# Mini_Voltmeter.net
KiCad netlist of a schematic drawn in Altium Designer
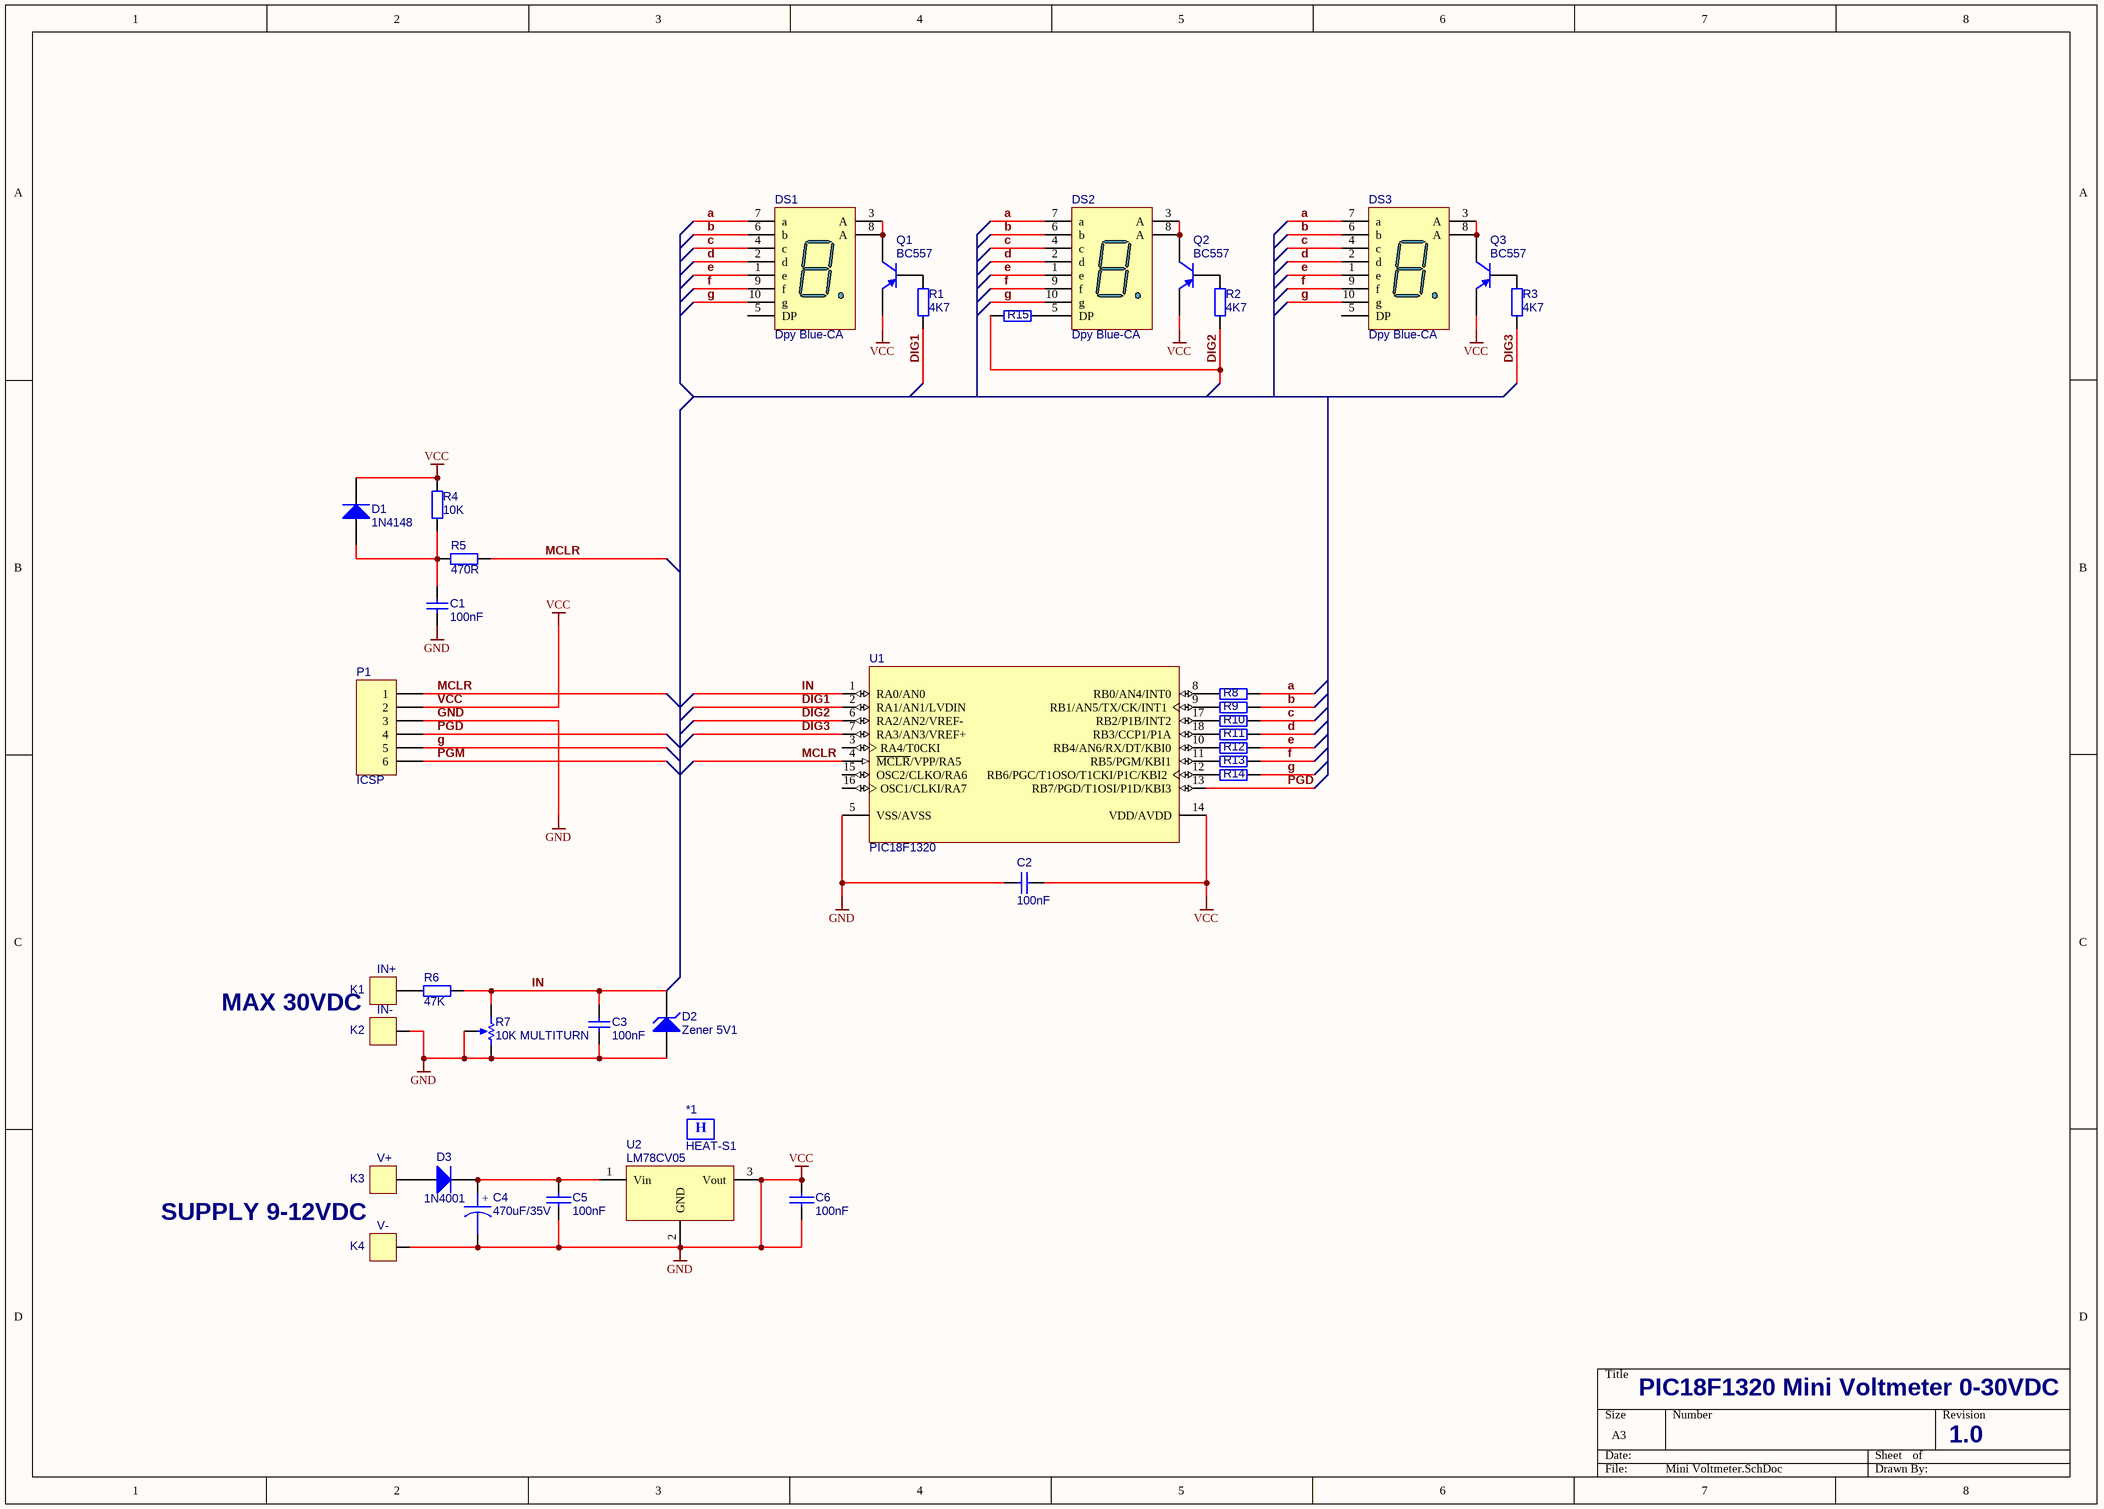
[diagram p0: Mini Voltmeter.SchDoc]

(export (version "E")
  (design (tool "Eeschema 10.0.6"))
  (components
    (comp (ref "*1")
      (value "HEAT-S1")
      (footprint "Heat_Sink1")
      (libsource (lib "SG_INTLIB") (part "HEAT-S1"))
    )
    (comp (ref "C1")
      (value "100nF")
      (footprint "RAD-0.3")
      (description "Capacitor")
      (fields (field (name "PUBLISHER") "Altium Limited"))
      (libsource (lib "Miscellaneous Devices") (part "Cap"))
    )
    (comp (ref "C2")
      (value "100nF")
      (footprint "RAD-0.3")
      (description "Capacitor")
      (fields (field (name "PUBLISHER") "Altium Limited"))
      (libsource (lib "Miscellaneous Devices") (part "Cap"))
    )
    (comp (ref "C3")
      (value "100nF")
      (footprint "RAD-0.3")
      (description "Capacitor")
      (fields (field (name "PUBLISHER") "Altium Limited"))
      (libsource (lib "Miscellaneous Devices") (part "Cap"))
    )
    (comp (ref "C4")
      (value "470uF/35V")
      (footprint "RB-10")
      (description "Capacitor")
      (libsource (lib "*") (part "CAPACITOR POL"))
    )
    (comp (ref "C5")
      (value "100nF")
      (footprint "RAD-0.1")
      (description "Capacitor")
      (libsource (lib "*") (part "CAP"))
    )
    (comp (ref "C6")
      (value "100nF")
      (footprint "RAD-0.1")
      (description "Capacitor")
      (libsource (lib "*") (part "CAP"))
    )
    (comp (ref "D1")
      (value "1N4148")
      (footprint "DO-35")
      (description "High Conductance Fast Diode")
      (fields (field (name "PUBLISHER") "Altium Limited"))
      (libsource (lib "Miscellaneous Devices") (part "Diode 1N914"))
    )
    (comp (ref "D2")
      (value "Zener 5V1")
      (description "Zener Diode")
      (fields (field (name "PUBLISHER") "Altium Limited"))
      (libsource (lib "Miscellaneous Devices") (part "D Zener"))
    )
    (comp (ref "D3")
      (value "1N4001")
      (footprint "DO-35")
      (description "High Conductance Fast Diode")
      (fields (field (name "PUBLISHER") "Altium Limited"))
      (libsource (lib "Miscellaneous Devices") (part "Diode 1N914"))
    )
    (comp (ref "DS1")
      (value "Dpy Blue-CA")
      (footprint "H")
      (description "14.2 mm General Purpose Blue 7-Segment Display: CA, RH DP, Gray Surface")
      (fields (field (name "PUBLISHER") "Altium Limited"))
      (libsource (lib "Miscellaneous Devices") (part "Dpy Blue-CA"))
    )
    (comp (ref "DS2")
      (value "Dpy Blue-CA")
      (footprint "H")
      (description "14.2 mm General Purpose Blue 7-Segment Display: CA, RH DP, Gray Surface")
      (fields (field (name "PUBLISHER") "Altium Limited"))
      (libsource (lib "Miscellaneous Devices") (part "Dpy Blue-CA"))
    )
    (comp (ref "DS3")
      (value "Dpy Blue-CA")
      (footprint "H")
      (description "14.2 mm General Purpose Blue 7-Segment Display: CA, RH DP, Gray Surface")
      (fields (field (name "PUBLISHER") "Altium Limited"))
      (libsource (lib "Miscellaneous Devices") (part "Dpy Blue-CA"))
    )
    (comp (ref "K1")
      (value "IN+")
      (footprint "CON2")
      (description "Connector")
      (libsource (lib "*") (part "CON1"))
    )
    (comp (ref "K2")
      (value "IN-")
      (footprint "CON2")
      (description "Connector")
      (libsource (lib "*") (part "CON1"))
    )
    (comp (ref "K3")
      (value "V+")
      (footprint "CON2")
      (description "Connector")
      (libsource (lib "*") (part "CON1"))
    )
    (comp (ref "K4")
      (value "V-")
      (footprint "CON2")
      (description "Connector")
      (libsource (lib "*") (part "CON1"))
    )
    (comp (ref "P1")
      (value "ICSP")
      (footprint "HDR1X6")
      (description "Header, 6-Pin")
      (fields (field (name "PUBLISHER") "Altium Limited"))
      (libsource (lib "Miscellaneous Connectors") (part "Header 6"))
    )
    (comp (ref "Q1")
      (value "BC557")
      (footprint "SOT54")
      (description "PNP General-purpose Transistor")
      (fields (field (name "PUBLISHER") "Altium Limited"))
      (libsource (lib "Philips Discrete BJT - Low Power") (part "BC557"))
    )
    (comp (ref "Q2")
      (value "BC557")
      (footprint "SOT54")
      (description "PNP General-purpose Transistor")
      (fields (field (name "PUBLISHER") "Altium Limited"))
      (libsource (lib "Philips Discrete BJT - Low Power") (part "BC557"))
    )
    (comp (ref "Q3")
      (value "BC557")
      (footprint "SOT54")
      (description "PNP General-purpose Transistor")
      (fields (field (name "PUBLISHER") "Altium Limited"))
      (libsource (lib "Philips Discrete BJT - Low Power") (part "BC557"))
    )
    (comp (ref "R1")
      (value "4K7")
      (footprint "AXIAL-0.4")
      (description "Resistor")
      (fields (field (name "PUBLISHER") "Altium Limited"))
      (libsource (lib "Miscellaneous Devices") (part "Res2"))
    )
    (comp (ref "R2")
      (value "4K7")
      (footprint "AXIAL-0.4")
      (description "Resistor")
      (fields (field (name "PUBLISHER") "Altium Limited"))
      (libsource (lib "Miscellaneous Devices") (part "Res2"))
    )
    (comp (ref "R3")
      (value "4K7")
      (footprint "AXIAL-0.4")
      (description "Resistor")
      (fields (field (name "PUBLISHER") "Altium Limited"))
      (libsource (lib "Miscellaneous Devices") (part "Res2"))
    )
    (comp (ref "R4")
      (value "10K")
      (footprint "AXIAL-0.4")
      (description "Resistor")
      (fields (field (name "PUBLISHER") "Altium Limited"))
      (libsource (lib "Miscellaneous Devices") (part "Res2"))
    )
    (comp (ref "R5")
      (value "470R")
      (footprint "AXIAL-0.4")
      (description "Resistor")
      (fields (field (name "PUBLISHER") "Altium Limited"))
      (libsource (lib "") (part "Res2_1"))
    )
    (comp (ref "R6")
      (value "47K")
      (footprint "AXIAL-0.4")
      (description "Resistor")
      (fields (field (name "PUBLISHER") "Altium Limited"))
      (libsource (lib "") (part "Res2_1"))
    )
    (comp (ref "R7")
      (value "10K MULTITURN")
      (footprint "VR5")
      (description "Potentiometer")
      (fields (field (name "PUBLISHER") "Altium Limited"))
      (libsource (lib "Miscellaneous Devices") (part "RPot"))
    )
    (comp (ref "R8")
      (value "220R")
      (footprint "AXIAL-0.4")
      (description "Resistor")
      (fields (field (name "PUBLISHER") "Altium Limited"))
      (libsource (lib "") (part "Res2_1"))
    )
    (comp (ref "R9")
      (value "220R")
      (footprint "AXIAL-0.4")
      (description "Resistor")
      (fields (field (name "PUBLISHER") "Altium Limited"))
      (libsource (lib "") (part "Res2_1"))
    )
    (comp (ref "R10")
      (value "220R")
      (footprint "AXIAL-0.4")
      (description "Resistor")
      (fields (field (name "PUBLISHER") "Altium Limited"))
      (libsource (lib "") (part "Res2_1"))
    )
    (comp (ref "R11")
      (value "220R")
      (footprint "AXIAL-0.4")
      (description "Resistor")
      (fields (field (name "PUBLISHER") "Altium Limited"))
      (libsource (lib "") (part "Res2_1"))
    )
    (comp (ref "R12")
      (value "220R")
      (footprint "AXIAL-0.4")
      (description "Resistor")
      (fields (field (name "PUBLISHER") "Altium Limited"))
      (libsource (lib "") (part "Res2_1"))
    )
    (comp (ref "R13")
      (value "220R")
      (footprint "AXIAL-0.4")
      (description "Resistor")
      (fields (field (name "PUBLISHER") "Altium Limited"))
      (libsource (lib "") (part "Res2_1"))
    )
    (comp (ref "R14")
      (value "220R")
      (footprint "AXIAL-0.4")
      (description "Resistor")
      (fields (field (name "PUBLISHER") "Altium Limited"))
      (libsource (lib "") (part "Res2_1"))
    )
    (comp (ref "R15")
      (value "220R")
      (footprint "AXIAL-0.4")
      (description "Resistor")
      (fields (field (name "PUBLISHER") "Altium Limited"))
      (libsource (lib "") (part "Res2_1"))
    )
    (comp (ref "U1")
      (value "PIC18F1320")
      (footprint "PDIP300-18")
      (fields (field (name "PUBLISHER") "Altium Limited"))
      (libsource (lib "Microchip Microcontroller 8-Bit PIC18") (part "PIC18F1320-E/P"))
    )
    (comp (ref "U2") (value "LM78CV05") (footprint "to-220") (libsource (lib "*") (part "VOLTREG")))
  )
  (nets
    (net (code "1") (name "/DIG1") (class "Default")
      (node (ref "R1") (pin "1") (pinfunction "1_1") (pintype "passive"))
      (node (ref "U1") (pin "2") (pinfunction "RA1/AN1/LVDIN_2") (pintype "bidirectional"))
    )
    (net (code "2") (name "/DIG2") (class "Default")
      (node (ref "R15") (pin "2") (pinfunction "2_2") (pintype "passive"))
      (node (ref "R2") (pin "1") (pinfunction "1_1") (pintype "passive"))
      (node (ref "U1") (pin "6") (pinfunction "RA2/AN2/VREF-_6") (pintype "bidirectional"))
    )
    (net (code "3") (name "/DIG3") (class "Default")
      (node (ref "R3") (pin "1") (pinfunction "1_1") (pintype "passive"))
      (node (ref "U1") (pin "7") (pinfunction "RA3/AN3/VREF+_7") (pintype "bidirectional"))
    )
    (net (code "4") (name "/IN") (class "Default")
      (node (ref "C3") (pin "2") (pinfunction "2_2") (pintype "passive"))
      (node (ref "D2") (pin "2") (pinfunction "K_2") (pintype "passive"))
      (node (ref "R6") (pin "1") (pinfunction "1_1") (pintype "passive"))
      (node (ref "R7") (pin "1") (pinfunction "TOP_1") (pintype "passive"))
      (node (ref "U1") (pin "1") (pinfunction "RA0/AN0_1") (pintype "bidirectional"))
    )
    (net (code "5") (name "/MCLR") (class "Default")
      (node (ref "P1") (pin "1") (pinfunction "1_1") (pintype "passive"))
      (node (ref "R5") (pin "1") (pinfunction "1_1") (pintype "passive"))
      (node (ref "U1") (pin "4") (pinfunction "~{MCLR}/VPP/RA5_4") (pintype "input"))
    )
    (net (code "6") (name "/PGD") (class "Default")
      (node (ref "P1") (pin "4") (pinfunction "4_4") (pintype "passive"))
      (node (ref "U1") (pin "13") (pinfunction "RB7/PGD/T1OSI/P1D/KBI3_13") (pintype "bidirectional"))
    )
    (net (code "7") (name "/PGM") (class "Default")
      (node (ref "P1") (pin "6") (pinfunction "6_6") (pintype "passive"))
    )
    (net (code "8") (name "/a") (class "Default")
      (node (ref "DS1") (pin "7") (pinfunction "a_7") (pintype "passive"))
      (node (ref "DS2") (pin "7") (pinfunction "a_7") (pintype "passive"))
      (node (ref "DS3") (pin "7") (pinfunction "a_7") (pintype "passive"))
      (node (ref "R8") (pin "1") (pinfunction "1_1") (pintype "passive"))
    )
    (net (code "9") (name "/b") (class "Default")
      (node (ref "DS1") (pin "6") (pinfunction "b_6") (pintype "passive"))
      (node (ref "DS2") (pin "6") (pinfunction "b_6") (pintype "passive"))
      (node (ref "DS3") (pin "6") (pinfunction "b_6") (pintype "passive"))
      (node (ref "R9") (pin "1") (pinfunction "1_1") (pintype "passive"))
    )
    (net (code "10") (name "/c") (class "Default")
      (node (ref "DS1") (pin "4") (pinfunction "c_4") (pintype "passive"))
      (node (ref "DS2") (pin "4") (pinfunction "c_4") (pintype "passive"))
      (node (ref "DS3") (pin "4") (pinfunction "c_4") (pintype "passive"))
      (node (ref "R10") (pin "1") (pinfunction "1_1") (pintype "passive"))
    )
    (net (code "11") (name "/d") (class "Default")
      (node (ref "DS1") (pin "2") (pinfunction "d_2") (pintype "passive"))
      (node (ref "DS2") (pin "2") (pinfunction "d_2") (pintype "passive"))
      (node (ref "DS3") (pin "2") (pinfunction "d_2") (pintype "passive"))
      (node (ref "R11") (pin "1") (pinfunction "1_1") (pintype "passive"))
    )
    (net (code "12") (name "/e") (class "Default")
      (node (ref "DS1") (pin "1") (pinfunction "e_1") (pintype "passive"))
      (node (ref "DS2") (pin "1") (pinfunction "e_1") (pintype "passive"))
      (node (ref "DS3") (pin "1") (pinfunction "e_1") (pintype "passive"))
      (node (ref "R12") (pin "1") (pinfunction "1_1") (pintype "passive"))
    )
    (net (code "13") (name "/f") (class "Default")
      (node (ref "DS1") (pin "9") (pinfunction "f_9") (pintype "passive"))
      (node (ref "DS2") (pin "9") (pinfunction "f_9") (pintype "passive"))
      (node (ref "DS3") (pin "9") (pinfunction "f_9") (pintype "passive"))
      (node (ref "R13") (pin "1") (pinfunction "1_1") (pintype "passive"))
    )
    (net (code "14") (name "/g") (class "Default")
      (node (ref "DS1") (pin "10") (pinfunction "g_10") (pintype "passive"))
      (node (ref "DS2") (pin "10") (pinfunction "g_10") (pintype "passive"))
      (node (ref "DS3") (pin "10") (pinfunction "g_10") (pintype "passive"))
      (node (ref "P1") (pin "5") (pinfunction "5_5") (pintype "passive"))
      (node (ref "R14") (pin "1") (pinfunction "1_1") (pintype "passive"))
    )
    (net (code "15") (name "GND") (class "Default")
      (node (ref "C1") (pin "1") (pinfunction "1_1") (pintype "passive"))
      (node (ref "C2") (pin "1") (pinfunction "1_1") (pintype "passive"))
      (node (ref "C2") (pin "2") (pinfunction "2_2") (pintype "passive"))
      (node (ref "C3") (pin "1") (pinfunction "1_1") (pintype "passive"))
      (node (ref "C4") (pin "2") (pinfunction "2_2") (pintype "passive"))
      (node (ref "C5") (pin "2") (pinfunction "2_2") (pintype "passive"))
      (node (ref "C6") (pin "1") (pinfunction "1_1") (pintype "passive"))
      (node (ref "C6") (pin "2") (pinfunction "2_2") (pintype "passive"))
      (node (ref "D1") (pin "2") (pinfunction "K_2") (pintype "passive"))
      (node (ref "D2") (pin "1") (pinfunction "A_1") (pintype "passive"))
      (node (ref "K2") (pin "1") (pinfunction "1_1") (pintype "passive"))
      (node (ref "K4") (pin "1") (pinfunction "1_1") (pintype "passive"))
      (node (ref "P1") (pin "2") (pinfunction "2_2") (pintype "passive"))
      (node (ref "P1") (pin "3") (pinfunction "3_3") (pintype "passive"))
      (node (ref "Q1") (pin "1") (pinfunction "E_1") (pintype "passive"))
      (node (ref "Q2") (pin "1") (pinfunction "E_1") (pintype "passive"))
      (node (ref "Q3") (pin "1") (pinfunction "E_1") (pintype "passive"))
      (node (ref "R4") (pin "2") (pinfunction "2_2") (pintype "passive"))
      (node (ref "R7") (pin "2") (pinfunction "BOT_2") (pintype "passive"))
      (node (ref "R7") (pin "3") (pinfunction "TAP_3") (pintype "passive"))
      (node (ref "U1") (pin "14") (pinfunction "VDD/AVDD_14") (pintype "power_in"))
      (node (ref "U1") (pin "5") (pinfunction "VSS/AVSS_5") (pintype "power_in"))
      (node (ref "U2") (pin "2") (pinfunction "GND_2") (pintype "passive"))
      (node (ref "U2") (pin "3") (pinfunction "Vout_3") (pintype "passive"))
    )
    (net (code "16") (name "Net-(D1-A)") (class "Default")
      (node (ref "C1") (pin "2") (pinfunction "2_2") (pintype "passive"))
      (node (ref "D1") (pin "1") (pinfunction "A_1") (pintype "passive"))
      (node (ref "R4") (pin "1") (pinfunction "1_1") (pintype "passive"))
      (node (ref "R5") (pin "2") (pinfunction "2_2") (pintype "passive"))
    )
    (net (code "17") (name "Net-(D3-A)") (class "Default")
      (node (ref "D3") (pin "1") (pinfunction "A_1") (pintype "passive"))
      (node (ref "K3") (pin "1") (pinfunction "1_1") (pintype "passive"))
    )
    (net (code "18") (name "Net-(D3-K)") (class "Default")
      (node (ref "C4") (pin "1") (pinfunction "1_1") (pintype "passive"))
      (node (ref "C5") (pin "1") (pinfunction "1_1") (pintype "passive"))
      (node (ref "D3") (pin "2") (pinfunction "K_2") (pintype "passive"))
      (node (ref "U2") (pin "1") (pinfunction "Vin_1") (pintype "passive"))
    )
    (net (code "19") (name "Net-(DS2-DP)") (class "Default")
      (node (ref "DS2") (pin "5") (pinfunction "DP_5") (pintype "passive"))
      (node (ref "R15") (pin "1") (pinfunction "1_1") (pintype "passive"))
    )
    (net (code "20") (name "Net-(K1-Pad1)") (class "Default")
      (node (ref "K1") (pin "1") (pinfunction "1_1") (pintype "passive"))
      (node (ref "R6") (pin "2") (pinfunction "2_2") (pintype "passive"))
    )
    (net (code "21") (name "Net-(Q1-B)") (class "Default")
      (node (ref "Q1") (pin "2") (pinfunction "B_2") (pintype "passive"))
      (node (ref "R1") (pin "2") (pinfunction "2_2") (pintype "passive"))
    )
    (net (code "22") (name "Net-(Q1-C)") (class "Default")
      (node (ref "DS1") (pin "3") (pinfunction "A_3") (pintype "passive"))
      (node (ref "DS1") (pin "8") (pinfunction "A_8") (pintype "passive"))
      (node (ref "Q1") (pin "3") (pinfunction "C_3") (pintype "passive"))
    )
    (net (code "23") (name "Net-(Q2-B)") (class "Default")
      (node (ref "Q2") (pin "2") (pinfunction "B_2") (pintype "passive"))
      (node (ref "R2") (pin "2") (pinfunction "2_2") (pintype "passive"))
    )
    (net (code "24") (name "Net-(Q2-C)") (class "Default")
      (node (ref "DS2") (pin "3") (pinfunction "A_3") (pintype "passive"))
      (node (ref "DS2") (pin "8") (pinfunction "A_8") (pintype "passive"))
      (node (ref "Q2") (pin "3") (pinfunction "C_3") (pintype "passive"))
    )
    (net (code "25") (name "Net-(Q3-B)") (class "Default")
      (node (ref "Q3") (pin "2") (pinfunction "B_2") (pintype "passive"))
      (node (ref "R3") (pin "2") (pinfunction "2_2") (pintype "passive"))
    )
    (net (code "26") (name "Net-(Q3-C)") (class "Default")
      (node (ref "DS3") (pin "3") (pinfunction "A_3") (pintype "passive"))
      (node (ref "DS3") (pin "8") (pinfunction "A_8") (pintype "passive"))
      (node (ref "Q3") (pin "3") (pinfunction "C_3") (pintype "passive"))
    )
    (net (code "27") (name "Net-(U1-RB0{slash}AN4{slash}INT0)") (class "Default")
      (node (ref "R8") (pin "2") (pinfunction "2_2") (pintype "passive"))
      (node (ref "U1") (pin "8") (pinfunction "RB0/AN4/INT0_8") (pintype "bidirectional"))
    )
    (net (code "28") (name "Net-(U1-RB1{slash}AN5{slash}TX{slash}CK{slash}INT1)") (class "Default")
      (node (ref "R9") (pin "2") (pinfunction "2_2") (pintype "passive"))
      (node (ref "U1") (pin "9") (pinfunction "RB1/AN5/TX/CK/INT1_9") (pintype "bidirectional"))
    )
    (net (code "29") (name "Net-(U1-RB2{slash}P1B{slash}INT2)") (class "Default")
      (node (ref "R10") (pin "2") (pinfunction "2_2") (pintype "passive"))
      (node (ref "U1") (pin "17") (pinfunction "RB2/P1B/INT2_17") (pintype "bidirectional"))
    )
    (net (code "30") (name "Net-(U1-RB3{slash}CCP1{slash}P1A)") (class "Default")
      (node (ref "R11") (pin "2") (pinfunction "2_2") (pintype "passive"))
      (node (ref "U1") (pin "18") (pinfunction "RB3/CCP1/P1A_18") (pintype "bidirectional"))
    )
    (net (code "31") (name "Net-(U1-RB4{slash}AN6{slash}RX{slash}DT{slash}KBI0)") (class "Default")
      (node (ref "R12") (pin "2") (pinfunction "2_2") (pintype "passive"))
      (node (ref "U1") (pin "10") (pinfunction "RB4/AN6/RX/DT/KBI0_10") (pintype "bidirectional"))
    )
    (net (code "32") (name "Net-(U1-RB5{slash}PGM{slash}KBI1)") (class "Default")
      (node (ref "R13") (pin "2") (pinfunction "2_2") (pintype "passive"))
      (node (ref "U1") (pin "11") (pinfunction "RB5/PGM/KBI1_11") (pintype "bidirectional"))
    )
    (net (code "33") (name "Net-(U1-RB6{slash}PGC{slash}T1OSO{slash}T1CKI{slash}P1C{slash}KBI2)") (class "Default")
      (node (ref "R14") (pin "2") (pinfunction "2_2") (pintype "passive"))
      (node (ref "U1") (pin "12") (pinfunction "RB6/PGC/T1OSO/T1CKI/P1C/KBI2_12") (pintype "bidirectional"))
    )
    (net (code "34") (name "unconnected-(DS1-DP-Pad5)") (class "Default")
      (node (ref "DS1") (pin "5") (pinfunction "DP_5") (pintype "passive"))
    )
    (net (code "35") (name "unconnected-(DS3-DP-Pad5)") (class "Default")
      (node (ref "DS3") (pin "5") (pinfunction "DP_5") (pintype "passive"))
    )
    (net (code "36") (name "unconnected-(U1-OSC1{slash}CLKI{slash}RA7-Pad16)") (class "Default")
      (node (ref "U1") (pin "16") (pinfunction "OSC1/CLKI/RA7_16") (pintype "bidirectional"))
    )
    (net (code "37") (name "unconnected-(U1-OSC2{slash}CLKO{slash}RA6-Pad15)") (class "Default")
      (node (ref "U1") (pin "15") (pinfunction "OSC2/CLKO/RA6_15") (pintype "bidirectional"))
    )
    (net (code "38") (name "unconnected-(U1-RA4{slash}T0CKI-Pad3)") (class "Default")
      (node (ref "U1") (pin "3") (pinfunction "RA4/T0CKI_3") (pintype "bidirectional"))
    )
  )
)
